# Copy_of_MB1137.net
KiCad netlist of a schematic drawn in Altium Designer
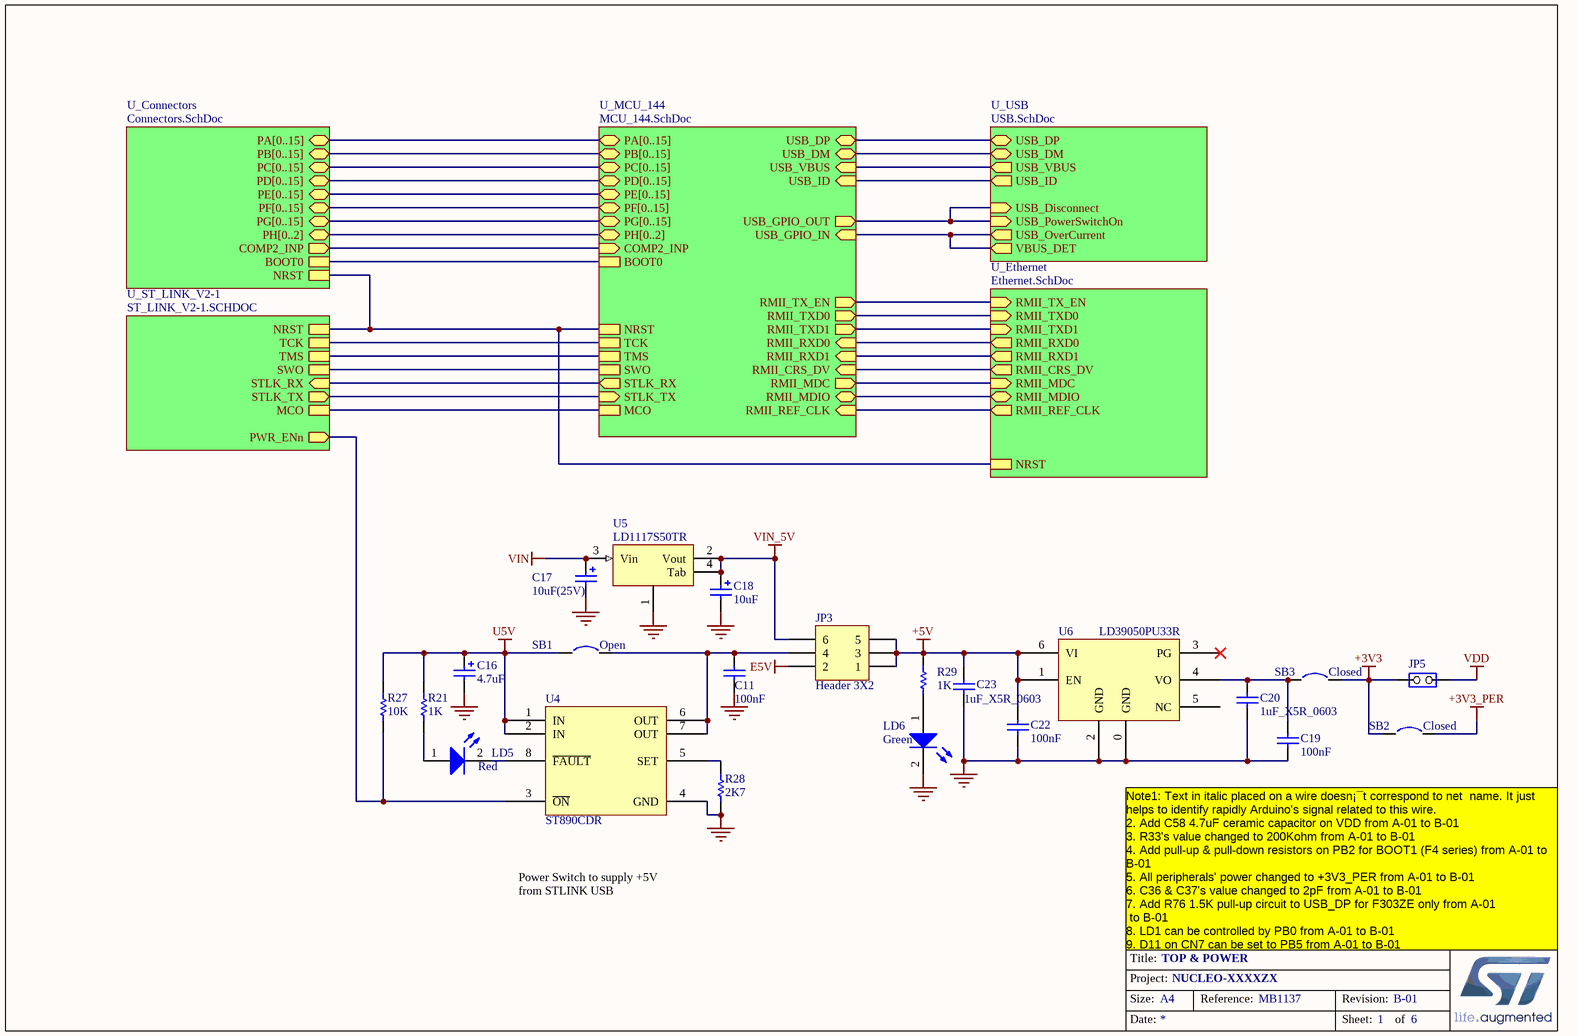
[diagram p0: Copy of MB1137.SchDoc]

(export (version "E")
  (design (tool "Eeschema 10.0.6"))
  (components
    (comp (ref "C11")
      (value "100nF")
      (footprint "0603C")
      (description "Capacitor 0402 / 0603 / 0805")
      (libsource (lib "MCD_TOOLS") (part "Capacitor_ST"))
    )
    (comp (ref "C16")
      (value "4.7uF")
      (footprint "TAN-A")
      (description "Polarized Capacitor (Radial)")
      (fields (field (name "PUBLISHER") "Altium Limited"))
      (libsource (lib "*") (part "Cap Pol1"))
    )
    (comp (ref "C17")
      (value "10uF(25V)")
      (footprint "TAN-B")
      (description "Polarized Capacitor (Radial)")
      (fields (field (name "PUBLISHER") "Altium Limited"))
      (libsource (lib "Miscellaneous Devices") (part "Cap Pol1"))
    )
    (comp (ref "C18")
      (value "10uF")
      (footprint "TAN-A")
      (description "Polarized Capacitor (Radial)")
      (fields (field (name "PUBLISHER") "Altium Limited"))
      (libsource (lib "Miscellaneous Devices") (part "Cap Pol1"))
    )
    (comp (ref "C19")
      (value "100nF")
      (footprint "0603C")
      (description "Capacitor 0402 / 0603 / 0805")
      (libsource (lib "MCD_TOOLS") (part "Capacitor_ST"))
    )
    (comp (ref "C20")
      (value "1uF_X5R_0603")
      (footprint "0603C")
      (description "0603  X5R 1µF")
      (fields (field (name "TOLERANCE") "10%"))
      (libsource (lib "MB963_1") (part "CAP SMD 0603  X5R 1µF 25V 10%"))
    )
    (comp (ref "C22")
      (value "100nF")
      (footprint "0603C")
      (description "Capacitor 0402 / 0603 / 0805")
      (libsource (lib "MCD_TOOLS") (part "Capacitor_ST"))
    )
    (comp (ref "C23")
      (value "1uF_X5R_0603")
      (footprint "0603C")
      (description "0603  X5R 1µF")
      (fields (field (name "TOLERANCE") "10%"))
      (libsource (lib "MB963_1") (part "CAP SMD 0603  X5R 1µF 25V 10%"))
    )
    (comp (ref "JP3")
      (value "Header 3X2")
      (footprint "HDR_3x2_2R54_V_M")
      (description "Header, 3-Pin, Dual row")
      (fields (field (name "PUBLISHER") "Altium Limited"))
      (libsource (lib "Miscellaneous Connectors") (part "Header 3X2"))
    )
    (comp (ref "JP5") (value "~") (footprint "HDR_1x2_2R54_V_M_S") (libsource (lib "*") (part "JP2")))
    (comp (ref "LD5")
      (value "Red")
      (footprint "0603D-R")
      (description "Typical RED, GREEN, YELLOW, AMBER GaAs LED")
      (fields (field (name "PUBLISHER") "Altium Limited"))
      (libsource (lib "Miscellaneous Devices") (part "LED2"))
    )
    (comp (ref "LD6")
      (value "Green")
      (footprint "0603D-G")
      (description "Typical RED, GREEN, YELLOW, AMBER GaAs LED")
      (fields (field (name "PUBLISHER") "Altium Limited"))
      (libsource (lib "") (part "LED2_1"))
    )
    (comp (ref "R21")
      (value "1K")
      (footprint "0603R")
      (description "Resistor")
      (fields (field (name "PUBLISHER") "Altium Limited"))
      (libsource (lib "*") (part "Res1"))
    )
    (comp (ref "R27")
      (value "10K")
      (footprint "STM-SMEE:0603R")
      (description "Resistor 0402 / 0603 / 0805")
      (libsource (lib "MCD_TOOLS") (part "Resistor_ST"))
    )
    (comp (ref "R28")
      (value "2K7")
      (footprint "STM-SMEE:0603R")
      (description "Resistor 0402 / 0603 / 0805")
      (libsource (lib "MCD_TOOLS") (part "Resistor_ST"))
    )
    (comp (ref "R29")
      (value "1K")
      (footprint "0603R")
      (description "Resistor 0402 / 0603 / 0805")
      (libsource (lib "MCD_TOOLS") (part "Resistor_ST"))
    )
    (comp (ref "SB1")
      (value "Open")
      (footprint "SB_0603")
      (description "Circuit Breaker")
      (fields (field (name "PUBLISHER") "Altium Limited"))
      (libsource (lib "MB1167") (part "Circuit Breaker"))
    )
    (comp (ref "SB2")
      (value "Closed")
      (footprint "SB_0603")
      (description "Circuit Breaker")
      (fields (field (name "PUBLISHER") "Altium Limited"))
      (libsource (lib "MB1167") (part "Circuit Breaker_close"))
    )
    (comp (ref "SB3")
      (value "Closed")
      (footprint "SB_0603")
      (description "Circuit Breaker")
      (fields (field (name "PUBLISHER") "Altium Limited"))
      (libsource (lib "MB1167") (part "Circuit Breaker_close"))
    )
    (comp (ref "U4")
      (value "ST890CDR")
      (footprint "SOIC8_1R27_4R9X6")
      (libsource (lib "MB1137") (part "ST890CDR"))
    )
    (comp (ref "U5") (value "LD1117S50TR") (footprint "SOT-223") (libsource (lib "MB1137") (part "LD1117")))
    (comp (ref "U6")
      (value "LD39050PU33R")
      (footprint "DFN6_0R95_3x3_TP")
      (libsource (lib "MB1137") (part "LD39050P"))
    )
  )
  (nets
    (net (code "1") (name "+3V3") (class "Default")
      (node (ref "JP5") (pin "1") (pinfunction "COMMON_1") (pintype "passive"))
      (node (ref "SB2") (pin "1") (pinfunction "1_1") (pintype "passive"))
      (node (ref "SB3") (pin "2") (pinfunction "2_2") (pintype "passive"))
    )
    (net (code "2") (name "+3V3_PER") (class "Default")
      (node (ref "SB2") (pin "2") (pinfunction "2_2") (pintype "passive"))
    )
    (net (code "3") (name "+5V") (class "Default")
      (node (ref "C22") (pin "2") (pinfunction "2_2") (pintype "passive"))
      (node (ref "C23") (pin "1") (pinfunction "1_1") (pintype "passive"))
      (node (ref "JP3") (pin "1") (pinfunction "1_1") (pintype "passive"))
      (node (ref "JP3") (pin "3") (pinfunction "3_3") (pintype "passive"))
      (node (ref "JP3") (pin "5") (pinfunction "5_5") (pintype "passive"))
      (node (ref "R29") (pin "2") (pinfunction "2_2") (pintype "passive"))
      (node (ref "U6") (pin "1") (pinfunction "EN_1") (pintype "passive"))
      (node (ref "U6") (pin "6") (pinfunction "VI_6") (pintype "passive"))
    )
    (net (code "16") (name "/PWR_ENn") (class "Default")
      (node (ref "R27") (pin "2") (pinfunction "2_2") (pintype "passive"))
      (node (ref "U4") (pin "3") (pinfunction "~{ON}_3") (pintype "passive"))
    )
    (net (code "37") (name "E5V") (class "Default")
      (node (ref "JP3") (pin "2") (pinfunction "2_2") (pintype "passive"))
    )
    (net (code "38") (name "GND") (class "Default")
      (node (ref "C11") (pin "1") (pinfunction "1_1") (pintype "passive"))
      (node (ref "C16") (pin "2") (pinfunction "2_2") (pintype "passive"))
      (node (ref "C17") (pin "2") (pinfunction "2_2") (pintype "passive"))
      (node (ref "C18") (pin "2") (pinfunction "2_2") (pintype "passive"))
      (node (ref "C19") (pin "1") (pinfunction "1_1") (pintype "passive"))
      (node (ref "C20") (pin "2") (pinfunction "2_2") (pintype "passive"))
      (node (ref "C22") (pin "1") (pinfunction "1_1") (pintype "passive"))
      (node (ref "C23") (pin "2") (pinfunction "2_2") (pintype "passive"))
      (node (ref "LD6") (pin "2") (pinfunction "K_2") (pintype "passive"))
      (node (ref "R28") (pin "1") (pinfunction "1_1") (pintype "passive"))
      (node (ref "U4") (pin "4") (pinfunction "GND_4") (pintype "passive"))
      (node (ref "U5") (pin "1") (pintype "passive"))
      (node (ref "U6") (pin "0") (pinfunction "GND_0") (pintype "passive"))
      (node (ref "U6") (pin "2") (pinfunction "GND_2") (pintype "passive"))
    )
    (net (code "39") (name "Net-(C11-Pad2)") (class "Default")
      (node (ref "C11") (pin "2") (pinfunction "2_2") (pintype "passive"))
      (node (ref "JP3") (pin "4") (pinfunction "4_4") (pintype "passive"))
      (node (ref "SB1") (pin "2") (pinfunction "2_2") (pintype "passive"))
      (node (ref "U4") (pin "6") (pinfunction "OUT_6") (pintype "passive"))
      (node (ref "U4") (pin "7") (pinfunction "OUT_7") (pintype "passive"))
    )
    (net (code "40") (name "Net-(LD5-A)") (class "Default")
      (node (ref "LD5") (pin "1") (pinfunction "A_1") (pintype "passive"))
      (node (ref "R21") (pin "2") (pinfunction "2_2") (pintype "passive"))
    )
    (net (code "41") (name "Net-(LD5-K)") (class "Default")
      (node (ref "LD5") (pin "2") (pinfunction "K_2") (pintype "passive"))
      (node (ref "U4") (pin "8") (pinfunction "~{FAULT}_8") (pintype "passive"))
    )
    (net (code "42") (name "Net-(LD6-A)") (class "Default")
      (node (ref "LD6") (pin "1") (pinfunction "A_1") (pintype "passive"))
      (node (ref "R29") (pin "1") (pinfunction "1_1") (pintype "passive"))
    )
    (net (code "43") (name "Net-(U4-SET)") (class "Default")
      (node (ref "R28") (pin "2") (pinfunction "2_2") (pintype "passive"))
      (node (ref "U4") (pin "5") (pinfunction "SET_5") (pintype "passive"))
    )
    (net (code "44") (name "Net-(U6-VO)") (class "Default")
      (node (ref "C19") (pin "2") (pinfunction "2_2") (pintype "passive"))
      (node (ref "C20") (pin "1") (pinfunction "1_1") (pintype "passive"))
      (node (ref "SB3") (pin "1") (pinfunction "1_1") (pintype "passive"))
      (node (ref "U6") (pin "4") (pinfunction "VO_4") (pintype "passive"))
    )
    (net (code "45") (name "U5V") (class "Default")
      (node (ref "C16") (pin "1") (pinfunction "1_1") (pintype "passive"))
      (node (ref "R21") (pin "1") (pinfunction "1_1") (pintype "passive"))
      (node (ref "R27") (pin "1") (pinfunction "1_1") (pintype "passive"))
      (node (ref "SB1") (pin "1") (pinfunction "1_1") (pintype "passive"))
      (node (ref "U4") (pin "1") (pinfunction "IN_1") (pintype "passive"))
      (node (ref "U4") (pin "2") (pinfunction "IN_2") (pintype "passive"))
    )
    (net (code "46") (name "VDD") (class "Default")
      (node (ref "JP5") (pin "2") (pinfunction "NO_2") (pintype "passive"))
    )
    (net (code "47") (name "VIN") (class "Default")
      (node (ref "C17") (pin "1") (pinfunction "1_1") (pintype "passive"))
      (node (ref "U5") (pin "3") (pinfunction "Vin_3") (pintype "input"))
    )
    (net (code "48") (name "VIN_5V") (class "Default")
      (node (ref "C18") (pin "1") (pinfunction "1_1") (pintype "passive"))
      (node (ref "JP3") (pin "6") (pinfunction "6_6") (pintype "passive"))
      (node (ref "U5") (pin "2") (pinfunction "Vout_2") (pintype "power_in"))
      (node (ref "U5") (pin "4") (pinfunction "Tab_4") (pintype "power_in"))
    )
    (net (code "49") (name "unconnected-(U6-NC-Pad5)") (class "Default")
      (node (ref "U6") (pin "5") (pinfunction "NC_5") (pintype "passive"))
    )
    (net (code "50") (name "unconnected-(U6-PG-Pad3)") (class "Default")
      (node (ref "U6") (pin "3") (pinfunction "PG_3") (pintype "passive+no_connect"))
    )
  )
)
